# RadCounterX4_SCH.net
KiCad netlist of a schematic drawn in Altium Designer
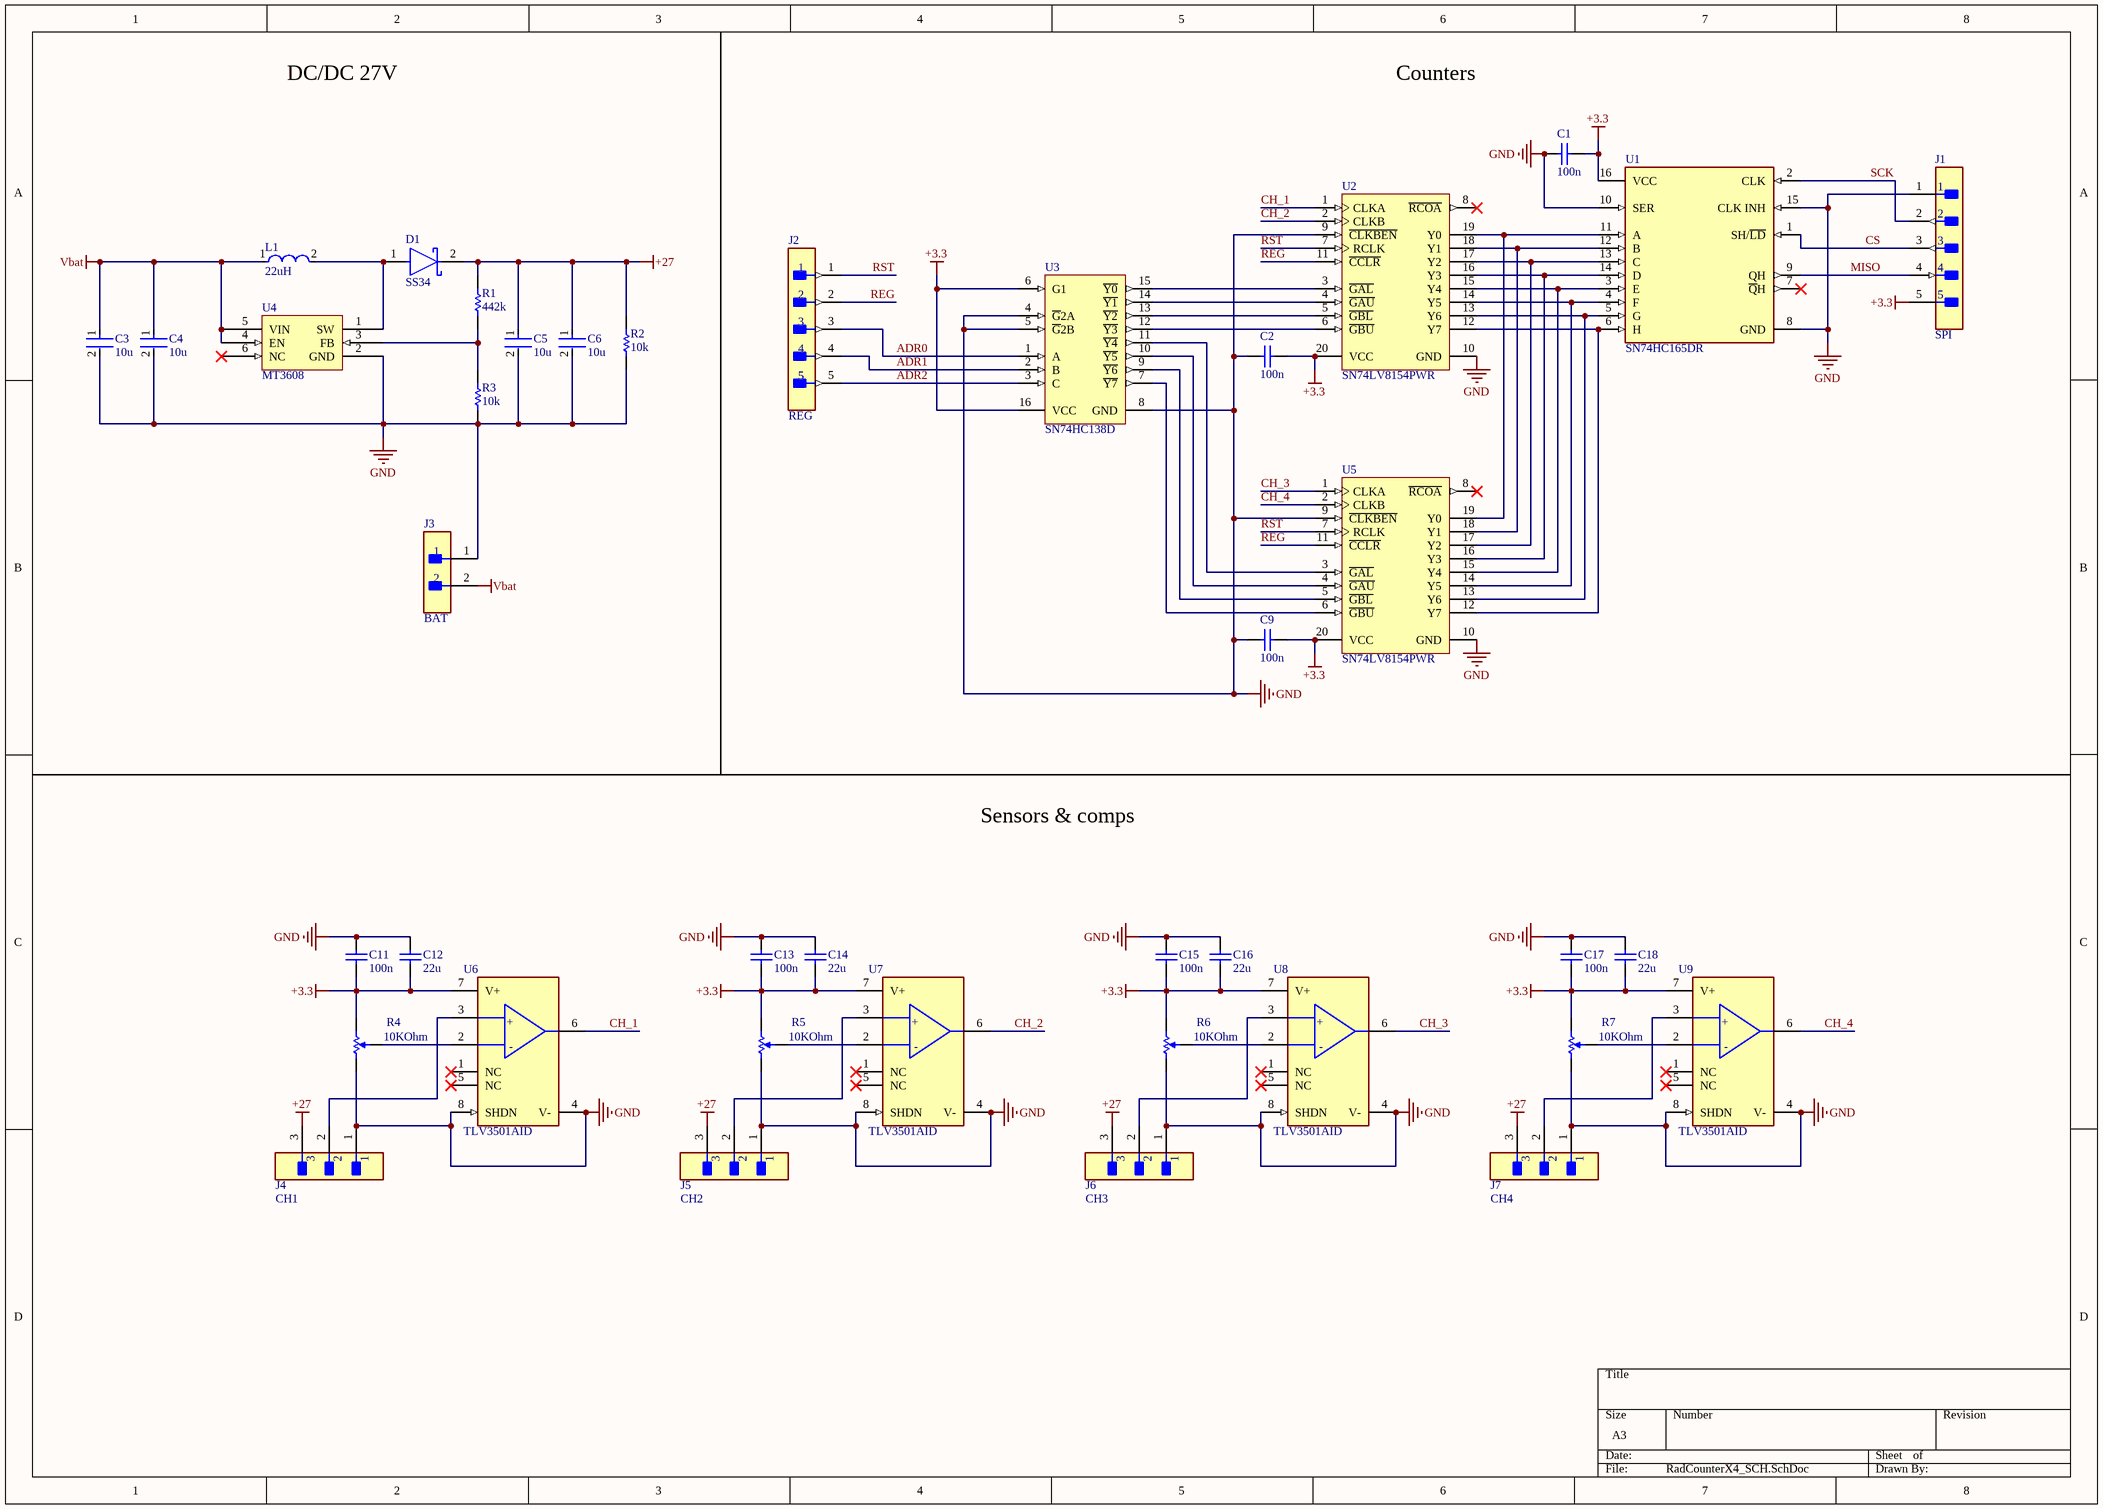
[diagram p0: RadCounterX4_SCH.SchDoc]

(export (version "E")
  (design (tool "Eeschema 10.0.6"))
  (components
    (comp (ref "C1")
      (value "100n")
      (footprint "C0603")
      (description "Generic SMD Capacitor")
      (libsource (lib "Essentials") (part "Capacitor"))
    )
    (comp (ref "C2")
      (value "100n")
      (footprint "C0402")
      (description "Generic SMD Capacitor")
      (libsource (lib "Essentials") (part "Capacitor"))
    )
    (comp (ref "C3")
      (value "10u")
      (footprint "FP-GRM32-MFG")
      (description "CAP CER 10UF 50V X7R 1210")
      (fields (field (name "TOLERANCE") "10%") (field (name "MANUFACTURER PART NUMBER") "GRM32ER71H106KA12L"))
      (libsource (lib "Altium Content Vault") (part "11868f565c42a9108669ba33697ecf6"))
    )
    (comp (ref "C4")
      (value "10u")
      (footprint "FP-GRM32-MFG")
      (description "CAP CER 10UF 50V X7R 1210")
      (fields (field (name "TOLERANCE") "10%") (field (name "MANUFACTURER PART NUMBER") "GRM32ER71H106KA12L"))
      (libsource (lib "Altium Content Vault") (part "11868f565c42a9108669ba33697ecf6"))
    )
    (comp (ref "C5")
      (value "10u")
      (footprint "FP-GRM32-MFG")
      (description "CAP CER 10UF 50V X7R 1210")
      (fields (field (name "TOLERANCE") "10%") (field (name "MANUFACTURER PART NUMBER") "GRM32ER71H106KA12L"))
      (libsource (lib "Altium Content Vault") (part "11868f565c42a9108669ba33697ecf6"))
    )
    (comp (ref "C6")
      (value "10u")
      (footprint "FP-GRM32-MFG")
      (description "CAP CER 10UF 50V X7R 1210")
      (fields (field (name "TOLERANCE") "10%") (field (name "MANUFACTURER PART NUMBER") "GRM32ER71H106KA12L"))
      (libsource (lib "Altium Content Vault") (part "11868f565c42a9108669ba33697ecf6"))
    )
    (comp (ref "C9")
      (value "100n")
      (footprint "C0402")
      (description "Generic SMD Capacitor")
      (libsource (lib "Essentials") (part "Capacitor"))
    )
    (comp (ref "C11")
      (value "100n")
      (footprint "C0603")
      (description "Generic SMD Capacitor")
      (libsource (lib "Essentials") (part "Capacitor"))
    )
    (comp (ref "C12")
      (value "22u")
      (footprint "C0603")
      (description "Generic SMD Capacitor")
      (libsource (lib "Essentials") (part "Capacitor"))
    )
    (comp (ref "C13")
      (value "100n")
      (footprint "C0603")
      (description "Generic SMD Capacitor")
      (libsource (lib "Essentials") (part "Capacitor"))
    )
    (comp (ref "C14")
      (value "22u")
      (footprint "C0603")
      (description "Generic SMD Capacitor")
      (libsource (lib "Essentials") (part "Capacitor"))
    )
    (comp (ref "C15")
      (value "100n")
      (footprint "C0603")
      (description "Generic SMD Capacitor")
      (libsource (lib "Essentials") (part "Capacitor"))
    )
    (comp (ref "C16")
      (value "22u")
      (footprint "C0603")
      (description "Generic SMD Capacitor")
      (libsource (lib "Essentials") (part "Capacitor"))
    )
    (comp (ref "C17")
      (value "100n")
      (footprint "C0603")
      (description "Generic SMD Capacitor")
      (libsource (lib "Essentials") (part "Capacitor"))
    )
    (comp (ref "C18")
      (value "22u")
      (footprint "C0603")
      (description "Generic SMD Capacitor")
      (libsource (lib "Essentials") (part "Capacitor"))
    )
    (comp (ref "D1")
      (value "SS34")
      (footprint "FP-403AE-MFG")
      (description "DIODE SCHOTTKY 40V 1A SMA")
      (fields
        (field (name "MANUFACTURER") "ON Semiconductor")
        (field (name "OCTOPART") "https://octopart.com/ss14-on+semiconductor-29205033")
      )
      (libsource (lib "Altium Content Vault") (part "360ad2f4ac25a952324d13796385471"))
    )
    (comp (ref "J1")
      (value "SPI")
      (footprint "FP-B5B-XH-AM_LF_SN-MFG")
      (description "CONN HEADER VERT 5POS 2.5MM")
      (libsource (lib "Altium Content Vault") (part "bf93c07fd2649a848d0ec8585582aab"))
    )
    (comp (ref "J2")
      (value "REG")
      (footprint "FP-B5B-XH-AM_LF_SN-MFG")
      (description "CONN HEADER VERT 5POS 2.5MM")
      (libsource (lib "") (part "bf93c07fd2649a848d0ec8585582aab_1"))
    )
    (comp (ref "J3")
      (value "BAT")
      (footprint "FP-B2B-XH-A_LF_SN-MFG")
      (description "CONN HEADER VERT 2POS 2.5MM")
      (libsource (lib "Altium Content Vault") (part "3bc925449376181038e59eaffc5286c"))
    )
    (comp (ref "J4")
      (value "CH1")
      (footprint "FP-B3B-XH-A_LF_SN-MFG")
      (description "CONN HEADER VERT 3POS 2.5MM")
      (libsource (lib "Altium Content Vault") (part "0d3f023dd272f625e17a2be33dea85f"))
    )
    (comp (ref "J5")
      (value "CH2")
      (footprint "FP-B3B-XH-A_LF_SN-MFG")
      (description "CONN HEADER VERT 3POS 2.5MM")
      (libsource (lib "Altium Content Vault") (part "0d3f023dd272f625e17a2be33dea85f"))
    )
    (comp (ref "J6")
      (value "CH3")
      (footprint "FP-B3B-XH-A_LF_SN-MFG")
      (description "CONN HEADER VERT 3POS 2.5MM")
      (libsource (lib "Altium Content Vault") (part "0d3f023dd272f625e17a2be33dea85f"))
    )
    (comp (ref "J7")
      (value "CH4")
      (footprint "FP-B3B-XH-A_LF_SN-MFG")
      (description "CONN HEADER VERT 3POS 2.5MM")
      (libsource (lib "Altium Content Vault") (part "0d3f023dd272f625e17a2be33dea85f"))
    )
    (comp (ref "L1")
      (value "22uH")
      (footprint "FP-IHLP-2525CZ-FP_2_413x3-MFG")
      (description "Commercial Inductors, Low DCR Series 22uH 2.9A 135mΩ 20%")
      (fields (field (name "TOLERANCE") "20%"))
      (libsource (lib "Altium Content Vault") (part "725321dda6339637d4d059423bc1c3c"))
    )
    (comp (ref "R1")
      (value "442k")
      (footprint "R0603")
      (description "Generic SMD Resistor")
      (libsource (lib "Essentials") (part "Resistor"))
    )
    (comp (ref "R2")
      (value "10k")
      (footprint "R0603")
      (description "Generic SMD Resistor")
      (libsource (lib "Essentials") (part "Resistor"))
    )
    (comp (ref "R3")
      (value "10k")
      (footprint "R0603")
      (description "Generic SMD Resistor")
      (libsource (lib "Essentials") (part "Resistor"))
    )
    (comp (ref "R4")
      (value "TC33X-2-103E")
      (footprint "BOUR-TC33X-2_V")
      (description "Trimming Potentiometer, 10000 Ohm, -40 to 100 degC, 3-Pin SMD, RoHS, Tape and Reel")
      (fields
        (field (name "TOLERANCE") "25%")
        (field (name "RESISTANCE") "10KOhm")
        (field (name "MANUFACTURER") "Bourns")
      )
      (libsource (lib "Altium Content Vault") (part "RES-ADJ-3_A"))
    )
    (comp (ref "R5")
      (value "TC33X-2-103E")
      (footprint "BOUR-TC33X-2_V")
      (description "Trimming Potentiometer, 10000 Ohm, -40 to 100 degC, 3-Pin SMD, RoHS, Tape and Reel")
      (fields
        (field (name "TOLERANCE") "25%")
        (field (name "RESISTANCE") "10KOhm")
        (field (name "MANUFACTURER") "Bourns")
      )
      (libsource (lib "Altium Content Vault") (part "RES-ADJ-3_A"))
    )
    (comp (ref "R6")
      (value "TC33X-2-103E")
      (footprint "BOUR-TC33X-2_V")
      (description "Trimming Potentiometer, 10000 Ohm, -40 to 100 degC, 3-Pin SMD, RoHS, Tape and Reel")
      (fields
        (field (name "TOLERANCE") "25%")
        (field (name "RESISTANCE") "10KOhm")
        (field (name "MANUFACTURER") "Bourns")
      )
      (libsource (lib "Altium Content Vault") (part "RES-ADJ-3_A"))
    )
    (comp (ref "R7")
      (value "TC33X-2-103E")
      (footprint "BOUR-TC33X-2_V")
      (description "Trimming Potentiometer, 10000 Ohm, -40 to 100 degC, 3-Pin SMD, RoHS, Tape and Reel")
      (fields
        (field (name "TOLERANCE") "25%")
        (field (name "RESISTANCE") "10KOhm")
        (field (name "MANUFACTURER") "Bourns")
      )
      (libsource (lib "Altium Content Vault") (part "RES-ADJ-3_A"))
    )
    (comp (ref "U1")
      (value "SN74HC165DR")
      (footprint "FP-D0016A-MFG")
      (description "IC 8-BIT SHIFT REGISTER 16-SOIC")
      (fields
        (field (name "MANUFACTURER") "Texas Instruments")
        (field (name "OCTOPART") "https://octopart.com/sn74hc165dr-texas+instruments-500689")
      )
      (libsource (lib "Altium Content Vault") (part "bec90d17a7f50c6d10a4b3032ae18cc"))
    )
    (comp (ref "U2")
      (value "SN74LV8154PWR")
      (footprint "PW0020A_N")
      (description "Dual 16-Bit Binary Counters with 3-State Output Registers, PW0020A, LARGE T&R")
      (fields
        (field (name "GENERIC PART NUMBER") "SN74LV8154")
        (field (name "MANUFACTURER") "Texas Instruments")
      )
      (libsource (lib "Altium Content Vault") (part "TI-SN74LV8154-20"))
    )
    (comp (ref "U3")
      (value "SN74HC138D")
      (footprint "D0016A_N")
      (description "3-Line To 8-Line Decoders/Demultiplexers, D0016A, TUBE")
      (fields
        (field (name "GENERIC PART NUMBER") "SN74HC138")
        (field (name "MANUFACTURER") "Texas Instruments")
      )
      (libsource (lib "Altium Content Vault") (part "TI-SNX4XXXX138-16"))
    )
    (comp (ref "U4")
      (value "MT3608")
      (footprint "SOT23")
      (description "2A, High Efficiency 1.2MHz Current Mode Step-Up Converter")
      (libsource (lib "Misc") (part "MT3608"))
    )
    (comp (ref "U5")
      (value "SN74LV8154PWR")
      (footprint "PW0020A_N")
      (description "Dual 16-Bit Binary Counters with 3-State Output Registers, PW0020A, LARGE T&R")
      (fields
        (field (name "GENERIC PART NUMBER") "SN74LV8154")
        (field (name "MANUFACTURER") "Texas Instruments")
      )
      (libsource (lib "Altium Content Vault") (part "TI-SN74LV8154-20"))
    )
    (comp (ref "U6")
      (value "TLV3501AID")
      (footprint "FP-D0008A-IPC_C")
      (description "IC COMPARATOR 4.5NS R-R HS 8SOIC")
      (libsource (lib "Altium Content Vault") (part "734816f6191e347792cdd10dde819a7"))
    )
    (comp (ref "U7")
      (value "TLV3501AID")
      (footprint "FP-D0008A-IPC_C")
      (description "IC COMPARATOR 4.5NS R-R HS 8SOIC")
      (libsource (lib "Altium Content Vault") (part "734816f6191e347792cdd10dde819a7"))
    )
    (comp (ref "U8")
      (value "TLV3501AID")
      (footprint "FP-D0008A-IPC_C")
      (description "IC COMPARATOR 4.5NS R-R HS 8SOIC")
      (libsource (lib "Altium Content Vault") (part "734816f6191e347792cdd10dde819a7"))
    )
    (comp (ref "U9")
      (value "TLV3501AID")
      (footprint "FP-D0008A-IPC_C")
      (description "IC COMPARATOR 4.5NS R-R HS 8SOIC")
      (libsource (lib "Altium Content Vault") (part "734816f6191e347792cdd10dde819a7"))
    )
  )
  (nets
    (net (code "1") (name "+3.3") (class "Default")
      (node (ref "C1") (pin "2") (pinfunction "2_2") (pintype "passive"))
      (node (ref "C11") (pin "1") (pinfunction "1_1") (pintype "passive"))
      (node (ref "C12") (pin "1") (pinfunction "1_1") (pintype "passive"))
      (node (ref "C13") (pin "1") (pinfunction "1_1") (pintype "passive"))
      (node (ref "C14") (pin "1") (pinfunction "1_1") (pintype "passive"))
      (node (ref "C15") (pin "1") (pinfunction "1_1") (pintype "passive"))
      (node (ref "C16") (pin "1") (pinfunction "1_1") (pintype "passive"))
      (node (ref "C17") (pin "1") (pinfunction "1_1") (pintype "passive"))
      (node (ref "C18") (pin "1") (pinfunction "1_1") (pintype "passive"))
      (node (ref "C2") (pin "2") (pinfunction "2_2") (pintype "passive"))
      (node (ref "C9") (pin "2") (pinfunction "2_2") (pintype "passive"))
      (node (ref "J1") (pin "5") (pinfunction "5_5") (pintype "power_in"))
      (node (ref "R4") (pin "3") (pinfunction "3_3") (pintype "passive"))
      (node (ref "R5") (pin "3") (pinfunction "3_3") (pintype "passive"))
      (node (ref "R6") (pin "3") (pinfunction "3_3") (pintype "passive"))
      (node (ref "R7") (pin "3") (pinfunction "3_3") (pintype "passive"))
      (node (ref "U1") (pin "16") (pinfunction "VCC_16") (pintype "power_in"))
      (node (ref "U2") (pin "20") (pinfunction "VCC_20") (pintype "power_in"))
      (node (ref "U3") (pin "16") (pinfunction "VCC_16") (pintype "power_in"))
      (node (ref "U3") (pin "6") (pinfunction "G1_6") (pintype "input"))
      (node (ref "U5") (pin "20") (pinfunction "VCC_20") (pintype "power_in"))
      (node (ref "U6") (pin "7") (pinfunction "V+_7") (pintype "power_in"))
      (node (ref "U7") (pin "7") (pinfunction "V+_7") (pintype "power_in"))
      (node (ref "U8") (pin "7") (pinfunction "V+_7") (pintype "power_in"))
      (node (ref "U9") (pin "7") (pinfunction "V+_7") (pintype "power_in"))
    )
    (net (code "2") (name "+27") (class "Default")
      (node (ref "C5") (pin "1") (pinfunction "1_1") (pintype "passive"))
      (node (ref "C6") (pin "1") (pinfunction "1_1") (pintype "passive"))
      (node (ref "D1") (pin "2") (pinfunction "C_2") (pintype "passive"))
      (node (ref "J4") (pin "3") (pinfunction "3_3") (pintype "power_in"))
      (node (ref "J5") (pin "3") (pinfunction "3_3") (pintype "power_in"))
      (node (ref "J6") (pin "3") (pinfunction "3_3") (pintype "power_in"))
      (node (ref "J7") (pin "3") (pinfunction "3_3") (pintype "power_in"))
      (node (ref "R1") (pin "1") (pinfunction "1_1") (pintype "passive"))
      (node (ref "R2") (pin "2") (pinfunction "2_2") (pintype "passive"))
    )
    (net (code "3") (name "/ADR0") (class "Default")
      (node (ref "J2") (pin "3") (pinfunction "3_3") (pintype "output"))
      (node (ref "U3") (pin "1") (pinfunction "A_1") (pintype "input"))
    )
    (net (code "4") (name "/ADR1") (class "Default")
      (node (ref "J2") (pin "4") (pinfunction "4_4") (pintype "output"))
      (node (ref "U3") (pin "2") (pinfunction "B_2") (pintype "input"))
    )
    (net (code "5") (name "/ADR2") (class "Default")
      (node (ref "J2") (pin "5") (pinfunction "5_5") (pintype "output"))
      (node (ref "U3") (pin "3") (pinfunction "C_3") (pintype "input"))
    )
    (net (code "6") (name "/CH_1") (class "Default")
      (node (ref "U2") (pin "1") (pinfunction "CLKA_1") (pintype "input"))
      (node (ref "U6") (pin "6") (pinfunction "OUT_6") (pintype "passive"))
    )
    (net (code "7") (name "/CH_2") (class "Default")
      (node (ref "U2") (pin "2") (pinfunction "CLKB_2") (pintype "input"))
      (node (ref "U7") (pin "6") (pinfunction "OUT_6") (pintype "passive"))
    )
    (net (code "8") (name "/CH_3") (class "Default")
      (node (ref "U5") (pin "1") (pinfunction "CLKA_1") (pintype "input"))
      (node (ref "U8") (pin "6") (pinfunction "OUT_6") (pintype "passive"))
    )
    (net (code "9") (name "/CH_4") (class "Default")
      (node (ref "U5") (pin "2") (pinfunction "CLKB_2") (pintype "input"))
      (node (ref "U9") (pin "6") (pinfunction "OUT_6") (pintype "passive"))
    )
    (net (code "10") (name "/CS") (class "Default")
      (node (ref "J1") (pin "3") (pinfunction "3_3") (pintype "output"))
      (node (ref "U1") (pin "1") (pinfunction "SH/~{LD}_1") (pintype "input"))
    )
    (net (code "11") (name "/MISO") (class "Default")
      (node (ref "J1") (pin "4") (pinfunction "4_4") (pintype "input"))
      (node (ref "U1") (pin "9") (pinfunction "QH_9") (pintype "output"))
    )
    (net (code "12") (name "/REG") (class "Default")
      (node (ref "J2") (pin "2") (pinfunction "2_2") (pintype "output"))
      (node (ref "U2") (pin "11") (pinfunction "~{CCLR}_11") (pintype "input"))
      (node (ref "U5") (pin "11") (pinfunction "~{CCLR}_11") (pintype "input"))
    )
    (net (code "13") (name "/RST") (class "Default")
      (node (ref "J2") (pin "1") (pinfunction "1_1") (pintype "output"))
      (node (ref "U2") (pin "7") (pinfunction "RCLK_7") (pintype "input"))
      (node (ref "U5") (pin "7") (pinfunction "RCLK_7") (pintype "input"))
    )
    (net (code "14") (name "/SCK") (class "Default")
      (node (ref "J1") (pin "2") (pinfunction "2_2") (pintype "output"))
      (node (ref "U1") (pin "2") (pinfunction "CLK_2") (pintype "input"))
    )
    (net (code "15") (name "GND") (class "Default")
      (node (ref "C1") (pin "1") (pinfunction "1_1") (pintype "passive"))
      (node (ref "C11") (pin "2") (pinfunction "2_2") (pintype "passive"))
      (node (ref "C12") (pin "2") (pinfunction "2_2") (pintype "passive"))
      (node (ref "C13") (pin "2") (pinfunction "2_2") (pintype "passive"))
      (node (ref "C14") (pin "2") (pinfunction "2_2") (pintype "passive"))
      (node (ref "C15") (pin "2") (pinfunction "2_2") (pintype "passive"))
      (node (ref "C16") (pin "2") (pinfunction "2_2") (pintype "passive"))
      (node (ref "C17") (pin "2") (pinfunction "2_2") (pintype "passive"))
      (node (ref "C18") (pin "2") (pinfunction "2_2") (pintype "passive"))
      (node (ref "C2") (pin "1") (pinfunction "1_1") (pintype "passive"))
      (node (ref "C3") (pin "2") (pinfunction "2_2") (pintype "passive"))
      (node (ref "C4") (pin "2") (pinfunction "2_2") (pintype "passive"))
      (node (ref "C5") (pin "2") (pinfunction "2_2") (pintype "passive"))
      (node (ref "C6") (pin "2") (pinfunction "2_2") (pintype "passive"))
      (node (ref "C9") (pin "1") (pinfunction "1_1") (pintype "passive"))
      (node (ref "J1") (pin "1") (pinfunction "1_1") (pintype "power_in"))
      (node (ref "J3") (pin "1") (pinfunction "1_1") (pintype "passive"))
      (node (ref "J4") (pin "1") (pinfunction "1_1") (pintype "power_in"))
      (node (ref "J5") (pin "1") (pinfunction "1_1") (pintype "power_in"))
      (node (ref "J6") (pin "1") (pinfunction "1_1") (pintype "power_in"))
      (node (ref "J7") (pin "1") (pinfunction "1_1") (pintype "power_in"))
      (node (ref "R2") (pin "1") (pinfunction "1_1") (pintype "passive"))
      (node (ref "R3") (pin "1") (pinfunction "1_1") (pintype "passive"))
      (node (ref "R4") (pin "1") (pinfunction "1_1") (pintype "passive"))
      (node (ref "R5") (pin "1") (pinfunction "1_1") (pintype "passive"))
      (node (ref "R6") (pin "1") (pinfunction "1_1") (pintype "passive"))
      (node (ref "R7") (pin "1") (pinfunction "1_1") (pintype "passive"))
      (node (ref "U1") (pin "10") (pinfunction "SER_10") (pintype "input"))
      (node (ref "U1") (pin "15") (pinfunction "CLK_INH_15") (pintype "input"))
      (node (ref "U1") (pin "8") (pinfunction "GND_8") (pintype "power_in"))
      (node (ref "U2") (pin "10") (pinfunction "GND_10") (pintype "power_in"))
      (node (ref "U2") (pin "9") (pinfunction "~{CLKBEN}_9") (pintype "input"))
      (node (ref "U3") (pin "4") (pinfunction "~{G}2A_4") (pintype "input"))
      (node (ref "U3") (pin "5") (pinfunction "~{G}2B_5") (pintype "input"))
      (node (ref "U3") (pin "8") (pinfunction "GND_8") (pintype "power_in"))
      (node (ref "U4") (pin "2") (pinfunction "GND_2") (pintype "power_in"))
      (node (ref "U5") (pin "10") (pinfunction "GND_10") (pintype "power_in"))
      (node (ref "U5") (pin "9") (pinfunction "~{CLKBEN}_9") (pintype "input"))
      (node (ref "U6") (pin "4") (pinfunction "V-_4") (pintype "power_in"))
      (node (ref "U6") (pin "8") (pinfunction "SHDN_8") (pintype "input"))
      (node (ref "U7") (pin "4") (pinfunction "V-_4") (pintype "power_in"))
      (node (ref "U7") (pin "8") (pinfunction "SHDN_8") (pintype "input"))
      (node (ref "U8") (pin "4") (pinfunction "V-_4") (pintype "power_in"))
      (node (ref "U8") (pin "8") (pinfunction "SHDN_8") (pintype "input"))
      (node (ref "U9") (pin "4") (pinfunction "V-_4") (pintype "power_in"))
      (node (ref "U9") (pin "8") (pinfunction "SHDN_8") (pintype "input"))
    )
    (net (code "16") (name "Net-(D1-A)") (class "Default")
      (node (ref "D1") (pin "1") (pinfunction "A_1") (pintype "passive"))
      (node (ref "L1") (pin "2") (pinfunction "2_2") (pintype "passive"))
      (node (ref "U4") (pin "1") (pinfunction "SW_1") (pintype "power_in"))
    )
    (net (code "17") (name "Net-(U1-A)") (class "Default")
      (node (ref "U1") (pin "11") (pinfunction "A_11") (pintype "input"))
      (node (ref "U2") (pin "19") (pinfunction "Y0_19") (pintype "tri_state"))
      (node (ref "U5") (pin "19") (pinfunction "Y0_19") (pintype "tri_state"))
    )
    (net (code "18") (name "Net-(U1-B)") (class "Default")
      (node (ref "U1") (pin "12") (pinfunction "B_12") (pintype "input"))
      (node (ref "U2") (pin "18") (pinfunction "Y1_18") (pintype "tri_state"))
      (node (ref "U5") (pin "18") (pinfunction "Y1_18") (pintype "tri_state"))
    )
    (net (code "19") (name "Net-(U1-C)") (class "Default")
      (node (ref "U1") (pin "13") (pinfunction "C_13") (pintype "input"))
      (node (ref "U2") (pin "17") (pinfunction "Y2_17") (pintype "tri_state"))
      (node (ref "U5") (pin "17") (pinfunction "Y2_17") (pintype "tri_state"))
    )
    (net (code "20") (name "Net-(U1-D)") (class "Default")
      (node (ref "U1") (pin "14") (pinfunction "D_14") (pintype "input"))
      (node (ref "U2") (pin "16") (pinfunction "Y3_16") (pintype "tri_state"))
      (node (ref "U5") (pin "16") (pinfunction "Y3_16") (pintype "tri_state"))
    )
    (net (code "21") (name "Net-(U1-E)") (class "Default")
      (node (ref "U1") (pin "3") (pinfunction "E_3") (pintype "input"))
      (node (ref "U2") (pin "15") (pinfunction "Y4_15") (pintype "tri_state"))
      (node (ref "U5") (pin "15") (pinfunction "Y4_15") (pintype "tri_state"))
    )
    (net (code "22") (name "Net-(U1-F)") (class "Default")
      (node (ref "U1") (pin "4") (pinfunction "F_4") (pintype "input"))
      (node (ref "U2") (pin "14") (pinfunction "Y5_14") (pintype "tri_state"))
      (node (ref "U5") (pin "14") (pinfunction "Y5_14") (pintype "tri_state"))
    )
    (net (code "23") (name "Net-(U1-G)") (class "Default")
      (node (ref "U1") (pin "5") (pinfunction "G_5") (pintype "input"))
      (node (ref "U2") (pin "13") (pinfunction "Y6_13") (pintype "tri_state"))
      (node (ref "U5") (pin "13") (pinfunction "Y6_13") (pintype "tri_state"))
    )
    (net (code "24") (name "Net-(U1-H)") (class "Default")
      (node (ref "U1") (pin "6") (pinfunction "H_6") (pintype "input"))
      (node (ref "U2") (pin "12") (pinfunction "Y7_12") (pintype "tri_state"))
      (node (ref "U5") (pin "12") (pinfunction "Y7_12") (pintype "tri_state"))
    )
    (net (code "25") (name "Net-(U2-~{GAL})") (class "Default")
      (node (ref "U2") (pin "3") (pinfunction "~{GAL}_3") (pintype "input"))
      (node (ref "U3") (pin "15") (pinfunction "~{Y0}_15") (pintype "output"))
    )
    (net (code "26") (name "Net-(U2-~{GAU})") (class "Default")
      (node (ref "U2") (pin "4") (pinfunction "~{GAU}_4") (pintype "input"))
      (node (ref "U3") (pin "14") (pinfunction "~{Y1}_14") (pintype "output"))
    )
    (net (code "27") (name "Net-(U2-~{GBL})") (class "Default")
      (node (ref "U2") (pin "5") (pinfunction "~{GBL}_5") (pintype "input"))
      (node (ref "U3") (pin "13") (pinfunction "~{Y2}_13") (pintype "output"))
    )
    (net (code "28") (name "Net-(U2-~{GBU})") (class "Default")
      (node (ref "U2") (pin "6") (pinfunction "~{GBU}_6") (pintype "input"))
      (node (ref "U3") (pin "12") (pinfunction "~{Y3}_12") (pintype "output"))
    )
    (net (code "29") (name "Net-(U3-~{Y4})") (class "Default")
      (node (ref "U3") (pin "11") (pinfunction "~{Y4}_11") (pintype "output"))
      (node (ref "U5") (pin "3") (pinfunction "~{GAL}_3") (pintype "input"))
    )
    (net (code "30") (name "Net-(U3-~{Y5})") (class "Default")
      (node (ref "U3") (pin "10") (pinfunction "~{Y5}_10") (pintype "output"))
      (node (ref "U5") (pin "4") (pinfunction "~{GAU}_4") (pintype "input"))
    )
    (net (code "31") (name "Net-(U3-~{Y6})") (class "Default")
      (node (ref "U3") (pin "9") (pinfunction "~{Y6}_9") (pintype "output"))
      (node (ref "U5") (pin "5") (pinfunction "~{GBL}_5") (pintype "input"))
    )
    (net (code "32") (name "Net-(U3-~{Y7})") (class "Default")
      (node (ref "U3") (pin "7") (pinfunction "~{Y7}_7") (pintype "output"))
      (node (ref "U5") (pin "6") (pinfunction "~{GBU}_6") (pintype "input"))
    )
    (net (code "33") (name "Net-(U4-FB)") (class "Default")
      (node (ref "R1") (pin "2") (pinfunction "2_2") (pintype "passive"))
      (node (ref "R3") (pin "2") (pinfunction "2_2") (pintype "passive"))
      (node (ref "U4") (pin "3") (pinfunction "FB_3") (pintype "input"))
    )
    (net (code "34") (name "Net-(U6-+IN)") (class "Default")
      (node (ref "J4") (pin "2") (pinfunction "2_2") (pintype "passive"))
      (node (ref "U6") (pin "3") (pinfunction "+IN_3") (pintype "tri_state"))
    )
    (net (code "35") (name "Net-(U6--IN)") (class "Default")
      (node (ref "R4") (pin "2") (pinfunction "2_2") (pintype "passive"))
      (node (ref "U6") (pin "2") (pinfunction "-IN_2") (pintype "tri_state"))
    )
    (net (code "36") (name "Net-(U7-+IN)") (class "Default")
      (node (ref "J5") (pin "2") (pinfunction "2_2") (pintype "passive"))
      (node (ref "U7") (pin "3") (pinfunction "+IN_3") (pintype "tri_state"))
    )
    (net (code "37") (name "Net-(U7--IN)") (class "Default")
      (node (ref "R5") (pin "2") (pinfunction "2_2") (pintype "passive"))
      (node (ref "U7") (pin "2") (pinfunction "-IN_2") (pintype "tri_state"))
    )
    (net (code "38") (name "Net-(U8-+IN)") (class "Default")
      (node (ref "J6") (pin "2") (pinfunction "2_2") (pintype "passive"))
      (node (ref "U8") (pin "3") (pinfunction "+IN_3") (pintype "tri_state"))
    )
    (net (code "39") (name "Net-(U8--IN)") (class "Default")
      (node (ref "R6") (pin "2") (pinfunction "2_2") (pintype "passive"))
      (node (ref "U8") (pin "2") (pinfunction "-IN_2") (pintype "tri_state"))
    )
    (net (code "40") (name "Net-(U9-+IN)") (class "Default")
      (node (ref "J7") (pin "2") (pinfunction "2_2") (pintype "passive"))
      (node (ref "U9") (pin "3") (pinfunction "+IN_3") (pintype "tri_state"))
    )
    (net (code "41") (name "Net-(U9--IN)") (class "Default")
      (node (ref "R7") (pin "2") (pinfunction "2_2") (pintype "passive"))
      (node (ref "U9") (pin "2") (pinfunction "-IN_2") (pintype "tri_state"))
    )
    (net (code "42") (name "Vbat") (class "Default")
      (node (ref "C3") (pin "1") (pinfunction "1_1") (pintype "passive"))
      (node (ref "C4") (pin "1") (pinfunction "1_1") (pintype "passive"))
      (node (ref "J3") (pin "2") (pinfunction "2_2") (pintype "passive"))
      (node (ref "L1") (pin "1") (pinfunction "1_1") (pintype "passive"))
      (node (ref "U4") (pin "4") (pinfunction "EN_4") (pintype "input"))
      (node (ref "U4") (pin "5") (pinfunction "VIN_5") (pintype "power_in"))
    )
    (net (code "43") (name "unconnected-(U1-~{Q}H-Pad7)") (class "Default")
      (node (ref "U1") (pin "7") (pinfunction "~{Q}H_7") (pintype "output+no_connect"))
    )
    (net (code "44") (name "unconnected-(U2-~{RCOA}-Pad8)") (class "Default")
      (node (ref "U2") (pin "8") (pinfunction "~{RCOA}_8") (pintype "output+no_connect"))
    )
    (net (code "45") (name "unconnected-(U4-NC-Pad6)") (class "Default")
      (node (ref "U4") (pin "6") (pinfunction "NC_6") (pintype "input+no_connect"))
    )
    (net (code "46") (name "unconnected-(U5-~{RCOA}-Pad8)") (class "Default")
      (node (ref "U5") (pin "8") (pinfunction "~{RCOA}_8") (pintype "output+no_connect"))
    )
    (net (code "47") (name "unconnected-(U6-NC-Pad1)") (class "Default")
      (node (ref "U6") (pin "1") (pinfunction "NC_1") (pintype "passive+no_connect"))
    )
    (net (code "48") (name "unconnected-(U6-NC-Pad5)") (class "Default")
      (node (ref "U6") (pin "5") (pinfunction "NC_5") (pintype "passive+no_connect"))
    )
    (net (code "49") (name "unconnected-(U7-NC-Pad1)") (class "Default")
      (node (ref "U7") (pin "1") (pinfunction "NC_1") (pintype "passive+no_connect"))
    )
    (net (code "50") (name "unconnected-(U7-NC-Pad5)") (class "Default")
      (node (ref "U7") (pin "5") (pinfunction "NC_5") (pintype "passive+no_connect"))
    )
    (net (code "51") (name "unconnected-(U8-NC-Pad1)") (class "Default")
      (node (ref "U8") (pin "1") (pinfunction "NC_1") (pintype "passive+no_connect"))
    )
    (net (code "52") (name "unconnected-(U8-NC-Pad5)") (class "Default")
      (node (ref "U8") (pin "5") (pinfunction "NC_5") (pintype "passive+no_connect"))
    )
    (net (code "53") (name "unconnected-(U9-NC-Pad1)") (class "Default")
      (node (ref "U9") (pin "1") (pinfunction "NC_1") (pintype "passive+no_connect"))
    )
    (net (code "54") (name "unconnected-(U9-NC-Pad5)") (class "Default")
      (node (ref "U9") (pin "5") (pinfunction "NC_5") (pintype "passive+no_connect"))
    )
  )
)
